# floorctrl_power.net
KiCad netlist of a schematic drawn in Altium Designer
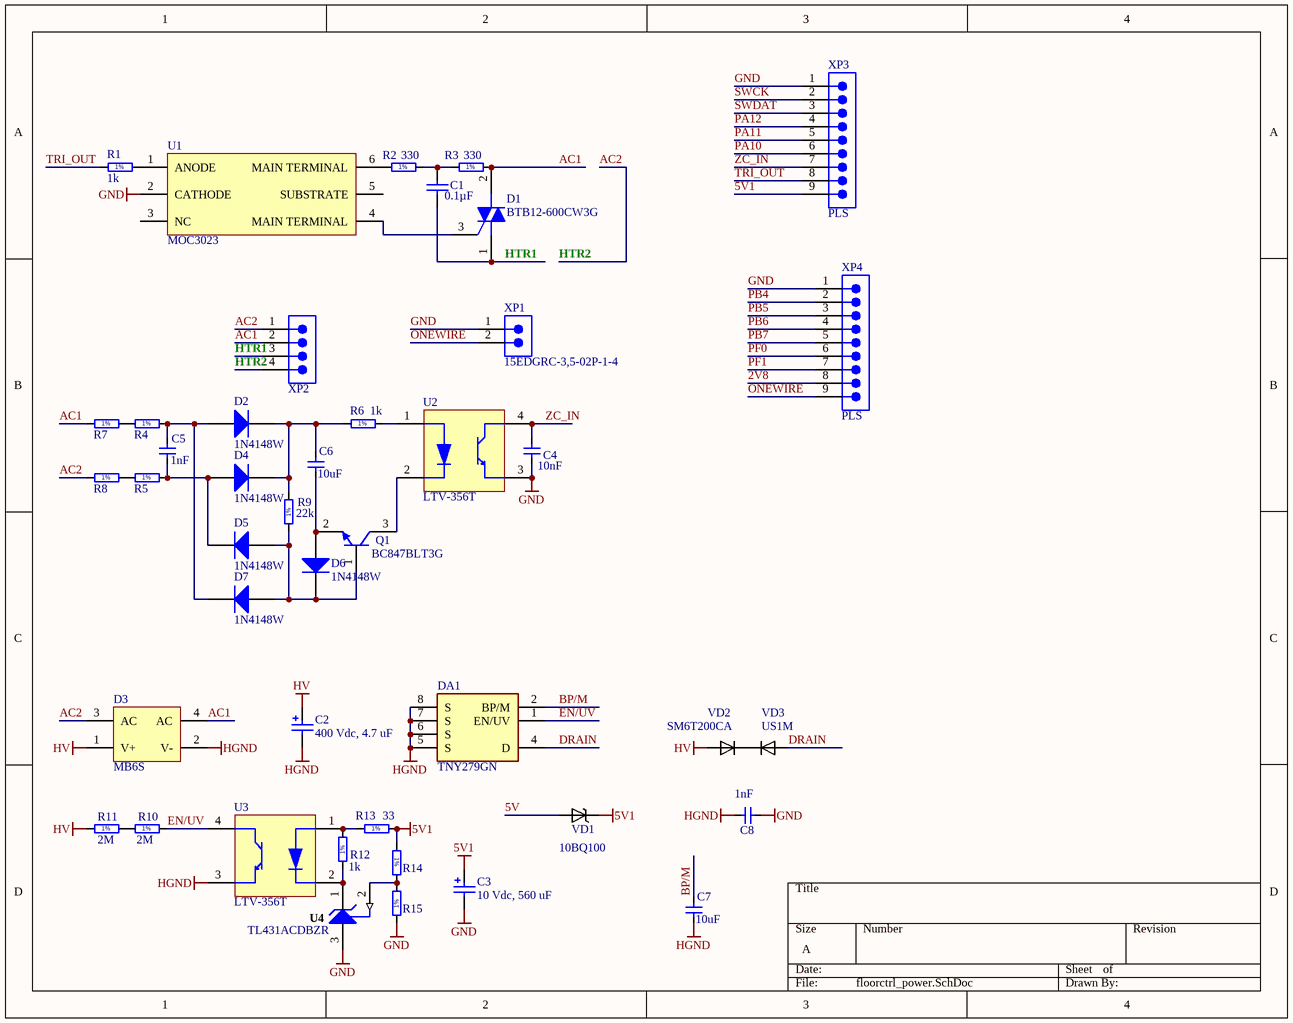
[diagram p0: floorctrl_power.SchDoc]

(export (version "E")
  (design (tool "Eeschema 10.0.6"))
  (components
    (comp (ref "C1")
      (value "A104M15X7RF5TAA")
      (footprint "CAPA55-380X260")
      (fields
        (field (name "MANUFACTURER") "Vishay")
        (field (name "CAPACITANCE") "0.1µF")
        (field (name "TOLERANCE") "±20%")
      )
      (libsource (lib "Altium Content Vault") (part "CAP-NP-2"))
    )
    (comp (ref "C2")
      (value "400 Vdc, 4.7 uF")
      (footprint "WCAP-ATG8_8x11.5x3.5")
      (description "WCAP-ATG8 Aluminum Electrolytic Capacitors, 8x11.5mm, 400 Vdc, 4.7 uF")
      (fields (field (name "PART NUMBER") "860011374005") (field (name "PUBLISHER") "Wurth Elektronik"))
      (libsource (lib "ALTIUM-WCAP-ATG8-rev17a") (part "860011374005"))
    )
    (comp (ref "C3")
      (value "10 Vdc, 560 uF")
      (footprint "WCAP-ATG8_8x11.5x3.5")
      (description "WCAP-ATG8 Aluminum Electrolytic Capacitors, 8x11.5mm, 10 Vdc, 560 uF")
      (fields (field (name "PART NUMBER") "860010274012") (field (name "PUBLISHER") "Wurth Elektronik"))
      (libsource (lib "ALTIUM-WCAP-ATG8-rev17a") (part "860010274012"))
    )
    (comp (ref "C4")
      (value "10nF")
      (footprint "CAP0805R")
      (fields
        (field (name "PART NUMBER") "CC0805_10NF_250V_10%_X7R")
        (field (name "VOLTAGE") "250V")
        (field (name "TOLERANCE") "±10%")
        (field (name "AUTHOR") "I. Kuznetsov")
      )
      (libsource (lib "Capacitor") (part "CAP_NON_POLAR"))
    )
    (comp (ref "C5")
      (value "1nF")
      (footprint "CAP0805R")
      (fields
        (field (name "PART NUMBER") "CC0805_1NF_50V_10%_X7R")
        (field (name "VOLTAGE") "50V")
        (field (name "TOLERANCE") "±10%")
        (field (name "AUTHOR") "I. Kuznetsov")
      )
      (libsource (lib "Capacitor") (part "CAP_NON_POLAR"))
    )
    (comp (ref "C6")
      (value "10uF")
      (footprint "CAP0805R")
      (fields
        (field (name "PART NUMBER") "CC0805_10UF_25V_10%_X5R")
        (field (name "VOLTAGE") "25V")
        (field (name "TOLERANCE") "±10%")
        (field (name "AUTHOR") "I. Kuznetsov")
      )
      (libsource (lib "Capacitor") (part "CAP_NON_POLAR"))
    )
    (comp (ref "C7")
      (value "10uF")
      (footprint "CAP0805R")
      (fields
        (field (name "PART NUMBER") "CC0805_10UF_25V_10%_X5R")
        (field (name "VOLTAGE") "25V")
        (field (name "TOLERANCE") "±10%")
        (field (name "AUTHOR") "I. Kuznetsov")
      )
      (libsource (lib "Capacitor") (part "CAP_NON_POLAR"))
    )
    (comp (ref "C8")
      (value "1nF")
      (footprint "CAP1206R")
      (fields
        (field (name "PART NUMBER") "CC1206_1NF_2KV_10%_X7R")
        (field (name "VOLTAGE") "2kV")
        (field (name "TOLERANCE") "±10%")
        (field (name "AUTHOR") "I. Kuznetsov")
      )
      (libsource (lib "Capacitor") (part "CAP_NON_POLAR"))
    )
    (comp (ref "D1")
      (value "BTB12-600CW3G")
      (footprint "ONSC-TO-220-3-221A-07")
      (description "Triacs, Silicon Bidirectional Thyristor, 3-Pin TO-220, Pb-Free, Tube")
      (fields (field (name "MANUFACTURER") "On Semiconductor"))
      (libsource (lib "Altium Content Vault") (part "ONSC-TRIAC-MT1MT2G-3"))
    )
    (comp (ref "D2")
      (value "1N4148W")
      (footprint "JSCJ-SOD-123-2_V")
      (description "Fast Switching Diode, 75 V, 150 mA, 2-Pin 2.7 x 1.6 x 1.25 mm SMD, Tape and Reel")
      (fields (field (name "MANUFACTURER") "Changjiang Electronics"))
      (libsource (lib "Altium Content Vault") (part "JSCJ-A1K2-2"))
    )
    (comp (ref "D3")
      (value "MB6S")
      (footprint "FAIR-MBXS_V")
      (description "Bridge Rectifier, 0.5 A, -55 to 150 degC, 4-Pin SMD, RoHS, Tape and Reel")
      (fields (field (name "MANUFACTURER") "FairchildSemiconductor"))
      (libsource (lib "Altium Content Vault") (part "FAIR-MBXS-4"))
    )
    (comp (ref "D4")
      (value "1N4148W")
      (footprint "JSCJ-SOD-123-2_V")
      (description "Fast Switching Diode, 75 V, 150 mA, 2-Pin 2.7 x 1.6 x 1.25 mm SMD, Tape and Reel")
      (fields (field (name "MANUFACTURER") "Changjiang Electronics"))
      (libsource (lib "Altium Content Vault") (part "JSCJ-A1K2-2"))
    )
    (comp (ref "D5")
      (value "1N4148W")
      (footprint "JSCJ-SOD-123-2_V")
      (description "Fast Switching Diode, 75 V, 150 mA, 2-Pin 2.7 x 1.6 x 1.25 mm SMD, Tape and Reel")
      (fields (field (name "MANUFACTURER") "Changjiang Electronics"))
      (libsource (lib "Altium Content Vault") (part "JSCJ-A1K2-2"))
    )
    (comp (ref "D6")
      (value "1N4148W")
      (footprint "JSCJ-SOD-123-2_V")
      (description "Fast Switching Diode, 75 V, 150 mA, 2-Pin 2.7 x 1.6 x 1.25 mm SMD, Tape and Reel")
      (fields (field (name "MANUFACTURER") "Changjiang Electronics"))
      (libsource (lib "Altium Content Vault") (part "JSCJ-A1K2-2"))
    )
    (comp (ref "D7")
      (value "1N4148W")
      (footprint "JSCJ-SOD-123-2_V")
      (description "Fast Switching Diode, 75 V, 150 mA, 2-Pin 2.7 x 1.6 x 1.25 mm SMD, Tape and Reel")
      (fields (field (name "MANUFACTURER") "Changjiang Electronics"))
      (libsource (lib "Altium Content Vault") (part "JSCJ-A1K2-2"))
    )
    (comp (ref "DA1")
      (value "TNY279GN")
      (footprint "SMDIP8")
      (libsource (lib "IC And Semiconductor") (part "TNY27x"))
    )
    (comp (ref "Q1")
      (value "BC847BLT3G")
      (footprint "ONSC-SOT-23-3-318-08_V")
      (description "General Purpose Transistor, NPN Silicon, 3-Pin SOT-23, Pb-Free, Tape and Reel")
      (fields (field (name "MANUFACTURER") "On Semiconductor"))
      (libsource (lib "Altium Content Vault") (part "ONSC-NPN-B1E2C3-3"))
    )
    (comp (ref "R1")
      (value "1k")
      (footprint "RES0805R")
      (fields
        (field (name "PART NUMBER") "R0805_1K_1%_0.125W_100PPM")
        (field (name "POWER") "0.125W")
        (field (name "TOLERANCE") "±1%")
        (field (name "AUTHOR") "CERN DEM JLC")
      )
      (libsource (lib "Resistor") (part "Resistor - 1%"))
    )
    (comp (ref "R2")
      (value "330")
      (footprint "RES0805R")
      (fields
        (field (name "PART NUMBER") "R0805_330R_1%_0.125W_100PPM")
        (field (name "POWER") "0.125W")
        (field (name "TOLERANCE") "±1%")
        (field (name "AUTHOR") "CERN DEM JLC")
      )
      (libsource (lib "Resistor") (part "Resistor - 1%"))
    )
    (comp (ref "R3")
      (value "330")
      (footprint "RES0805R")
      (fields
        (field (name "PART NUMBER") "R0805_330R_1%_0.125W_100PPM")
        (field (name "POWER") "0.125W")
        (field (name "TOLERANCE") "±1%")
        (field (name "AUTHOR") "CERN DEM JLC")
      )
      (libsource (lib "Resistor") (part "Resistor - 1%"))
    )
    (comp (ref "R4")
      (value "220k")
      (footprint "RES1206R")
      (fields
        (field (name "PART NUMBER") "R1206_220K_1%_0.25W_100PPM")
        (field (name "POWER") "0.25W")
        (field (name "TOLERANCE") "±1%")
        (field (name "AUTHOR") "CERN DEM JLC")
      )
      (libsource (lib "Resistor") (part "Resistor - 1%"))
    )
    (comp (ref "R5")
      (value "220k")
      (footprint "RES1206R")
      (fields
        (field (name "PART NUMBER") "R1206_220K_1%_0.25W_100PPM")
        (field (name "POWER") "0.25W")
        (field (name "TOLERANCE") "±1%")
        (field (name "AUTHOR") "CERN DEM JLC")
      )
      (libsource (lib "Resistor") (part "Resistor - 1%"))
    )
    (comp (ref "R6")
      (value "1k")
      (footprint "RES0805R")
      (fields
        (field (name "PART NUMBER") "R0805_1K_1%_0.125W_100PPM")
        (field (name "POWER") "0.125W")
        (field (name "TOLERANCE") "±1%")
        (field (name "AUTHOR") "CERN DEM JLC")
      )
      (libsource (lib "Resistor") (part "Resistor - 1%"))
    )
    (comp (ref "R7")
      (value "220k")
      (footprint "RES1206R")
      (fields
        (field (name "PART NUMBER") "R1206_220K_1%_0.25W_100PPM")
        (field (name "POWER") "0.25W")
        (field (name "TOLERANCE") "±1%")
        (field (name "AUTHOR") "CERN DEM JLC")
      )
      (libsource (lib "Resistor") (part "Resistor - 1%"))
    )
    (comp (ref "R8")
      (value "220k")
      (footprint "RES1206R")
      (fields
        (field (name "PART NUMBER") "R1206_220K_1%_0.25W_100PPM")
        (field (name "POWER") "0.25W")
        (field (name "TOLERANCE") "±1%")
        (field (name "AUTHOR") "CERN DEM JLC")
      )
      (libsource (lib "Resistor") (part "Resistor - 1%"))
    )
    (comp (ref "R9")
      (value "22k")
      (footprint "RES0805R")
      (fields
        (field (name "PART NUMBER") "R0805_22K_1%_0.125W_100PPM")
        (field (name "POWER") "0.125W")
        (field (name "TOLERANCE") "±1%")
        (field (name "AUTHOR") "CERN DEM JLC")
      )
      (libsource (lib "Resistor") (part "Resistor - 1%"))
    )
    (comp (ref "R10")
      (value "2M")
      (footprint "RES1206R")
      (fields
        (field (name "PART NUMBER") "R1206_2M_1%_0.25W_100PPM")
        (field (name "POWER") "0.25W")
        (field (name "TOLERANCE") "±1%")
        (field (name "AUTHOR") "CERN DEM JLC")
      )
      (libsource (lib "Resistor") (part "Resistor - 1%"))
    )
    (comp (ref "R11")
      (value "2M")
      (footprint "RES1206R")
      (fields
        (field (name "PART NUMBER") "R1206_2M_1%_0.25W_100PPM")
        (field (name "POWER") "0.25W")
        (field (name "TOLERANCE") "±1%")
        (field (name "AUTHOR") "CERN DEM JLC")
      )
      (libsource (lib "Resistor") (part "Resistor - 1%"))
    )
    (comp (ref "R12")
      (value "1k")
      (footprint "RES0805R")
      (fields
        (field (name "PART NUMBER") "R0805_1K_1%_0.125W_100PPM")
        (field (name "POWER") "0.125W")
        (field (name "TOLERANCE") "±1%")
        (field (name "AUTHOR") "CERN DEM JLC")
      )
      (libsource (lib "Resistor") (part "Resistor - 1%"))
    )
    (comp (ref "R13")
      (value "33")
      (footprint "RES0805R")
      (fields
        (field (name "PART NUMBER") "R0805_33R_1%_0.125W_100PPM")
        (field (name "POWER") "0.125W")
        (field (name "TOLERANCE") "±1%")
        (field (name "AUTHOR") "CERN DEM JLC")
      )
      (libsource (lib "Resistor") (part "Resistor - 1%"))
    )
    (comp (ref "R14")
      (value "10k")
      (footprint "RES0805R")
      (fields
        (field (name "PART NUMBER") "R0805_10K_1%_0.125W_100PPM")
        (field (name "POWER") "0.125W")
        (field (name "TOLERANCE") "±1%")
        (field (name "AUTHOR") "CERN DEM JLC")
      )
      (libsource (lib "Resistor") (part "Resistor - 1%"))
    )
    (comp (ref "R15")
      (value "9k1")
      (footprint "RES0805R")
      (fields
        (field (name "PART NUMBER") "R0805_9K1_1%_0.125W_100PPM")
        (field (name "POWER") "0.125W")
        (field (name "TOLERANCE") "±1%")
        (field (name "AUTHOR") "CERN DEM JLC")
      )
      (libsource (lib "Resistor") (part "Resistor - 1%"))
    )
    (comp (ref "U1")
      (value "MOC3023")
      (footprint "LTST-DIP-6")
      (description "Optocoupler Triac, 50 mA, -40 to 100 degC, 6-Pin DIP, RoHS, Tube")
      (fields (field (name "MANUFACTURER") "Lite-On-Inc."))
      (libsource (lib "Altium Content Vault") (part "LTST-MOC3063-DIP-6"))
    )
    (comp (ref "U2")
      (value "LTV-356T")
      (footprint "LTST-LTV-356T-4_V")
      (description "Optocoupler DC-IN 1-CH Transistor DC-OUT 4-Pin Mini-Flat")
      (fields (field (name "MANUFACTURER") "Lite-On"))
      (libsource (lib "") (part "LTST-LTV-356T-4_1"))
    )
    (comp (ref "U3")
      (value "LTV-356T")
      (footprint "LTST-LTV-356T-4_V")
      (description "Optocoupler DC-IN 1-CH Transistor DC-OUT 4-Pin Mini-Flat")
      (fields (field (name "MANUFACTURER") "Lite-On"))
      (libsource (lib "Altium Content Vault") (part "LTST-LTV-356T-4"))
    )
    (comp (ref "U4")
      (value "TL431ACDBZR")
      (footprint "DBZ0003A_L")
      (fields (field (name "MANUFACTURER") "Texas Instruments"))
      (libsource (lib "Altium Content Vault") (part "TI-TL431ADBZ3"))
    )
    (comp (ref "VD1")
      (value "10BQ100")
      (footprint "DO-214AA")
      (libsource (lib "IC And Semiconductor") (part "Diode - Schottky"))
    )
    (comp (ref "VD2")
      (value "SM6T200CA")
      (footprint "SMB")
      (libsource (lib "IC And Semiconductor") (part "Diode - General"))
    )
    (comp (ref "VD3")
      (value "US1M")
      (footprint "SMA")
      (libsource (lib "IC And Semiconductor") (part "Diode - General"))
    )
    (comp (ref "XP1")
      (value "15EDGRC-3,5-02P-1-4")
      (footprint "15EDGRC-3,5-02P-1-4")
      (libsource (lib "Connector") (part "CN_02P_1W"))
    )
    (comp (ref "XP2")
      (value "15EDGRC-3.5-04P-14")
      (footprint "15EDGRC-3.5-04P")
      (fields (field (name "PART NUMBER") "15EDGRC-3.65-04P-14"))
      (libsource (lib "Connector") (part "CN_04P_1W"))
    )
    (comp (ref "XP3")
      (value "PLS")
      (footprint "PLS-09")
      (fields (field (name "PART NUMBER") "PLS-09") (field (name "MANUFACTURER") "AUK"))
      (libsource (lib "Connector") (part "CN_09P_1W"))
    )
    (comp (ref "XP4")
      (value "PLS")
      (footprint "PLS-09")
      (fields (field (name "PART NUMBER") "PLS-09") (field (name "MANUFACTURER") "AUK"))
      (libsource (lib "Connector") (part "CN_09P_1W"))
    )
  )
  (nets
    (net (code "1") (name "/2V8") (class "Default")
      (node (ref "XP4") (pin "8") (pinfunction "8_8") (pintype "passive"))
    )
    (net (code "2") (name "/5V") (class "Default")
      (node (ref "VD1") (pin "A") (pinfunction "A_A") (pintype "passive"))
    )
    (net (code "3") (name "/AC1") (class "Default")
      (node (ref "D1") (pin "2") (pinfunction "MT2_2") (pintype "passive"))
      (node (ref "D3") (pin "4") (pinfunction "AC_4") (pintype "power_in"))
      (node (ref "R3") (pin "2") (pinfunction "2_2") (pintype "passive"))
      (node (ref "R7") (pin "1") (pinfunction "1_1") (pintype "passive"))
      (node (ref "XP2") (pin "2") (pinfunction "2_2") (pintype "passive"))
    )
    (net (code "4") (name "/AC2") (class "Default")
      (node (ref "D3") (pin "3") (pinfunction "AC_3") (pintype "power_in"))
      (node (ref "R8") (pin "1") (pinfunction "1_1") (pintype "passive"))
      (node (ref "XP2") (pin "1") (pinfunction "1_1") (pintype "passive"))
      (node (ref "XP2") (pin "4") (pinfunction "4_4") (pintype "passive"))
    )
    (net (code "5") (name "/BP{slash}M") (class "Default")
      (node (ref "C7") (pin "2") (pinfunction "2_2") (pintype "passive"))
      (node (ref "DA1") (pin "2") (pinfunction "BP/M_2") (pintype "passive"))
    )
    (net (code "6") (name "/DRAIN") (class "Default")
      (node (ref "DA1") (pin "4") (pinfunction "D_4") (pintype "passive"))
      (node (ref "VD3") (pin "A") (pinfunction "A_A") (pintype "passive"))
    )
    (net (code "7") (name "/EN{slash}UV") (class "Default")
      (node (ref "DA1") (pin "1") (pinfunction "EN/UV_1") (pintype "passive"))
      (node (ref "R10") (pin "2") (pinfunction "2_2") (pintype "passive"))
      (node (ref "U3") (pin "4") (pinfunction "COLLECTOR_4") (pintype "passive"))
    )
    (net (code "8") (name "/HTR1") (class "Default")
      (node (ref "C1") (pin "1") (pinfunction "1_1") (pintype "passive"))
      (node (ref "D1") (pin "1") (pinfunction "MT1_1") (pintype "passive"))
      (node (ref "XP2") (pin "3") (pinfunction "3_3") (pintype "passive"))
    )
    (net (code "9") (name "/ONEWIRE") (class "Default")
      (node (ref "XP1") (pin "2") (pinfunction "2_2") (pintype "passive"))
      (node (ref "XP4") (pin "9") (pinfunction "9_9") (pintype "passive"))
    )
    (net (code "10") (name "/PA10") (class "Default")
      (node (ref "XP3") (pin "6") (pinfunction "6_6") (pintype "passive"))
    )
    (net (code "11") (name "/PA11") (class "Default")
      (node (ref "XP3") (pin "5") (pinfunction "5_5") (pintype "passive"))
    )
    (net (code "12") (name "/PA12") (class "Default")
      (node (ref "XP3") (pin "4") (pinfunction "4_4") (pintype "passive"))
    )
    (net (code "13") (name "/PB4") (class "Default")
      (node (ref "XP4") (pin "2") (pinfunction "2_2") (pintype "passive"))
    )
    (net (code "14") (name "/PB5") (class "Default")
      (node (ref "XP4") (pin "3") (pinfunction "3_3") (pintype "passive"))
    )
    (net (code "15") (name "/PB6") (class "Default")
      (node (ref "XP4") (pin "4") (pinfunction "4_4") (pintype "passive"))
    )
    (net (code "16") (name "/PB7") (class "Default")
      (node (ref "XP4") (pin "5") (pinfunction "5_5") (pintype "passive"))
    )
    (net (code "17") (name "/PF0") (class "Default")
      (node (ref "XP4") (pin "6") (pinfunction "6_6") (pintype "passive"))
    )
    (net (code "18") (name "/PF1") (class "Default")
      (node (ref "XP4") (pin "7") (pinfunction "7_7") (pintype "passive"))
    )
    (net (code "19") (name "/SWCK") (class "Default")
      (node (ref "XP3") (pin "2") (pinfunction "2_2") (pintype "passive"))
    )
    (net (code "20") (name "/SWDAT") (class "Default")
      (node (ref "XP3") (pin "3") (pinfunction "3_3") (pintype "passive"))
    )
    (net (code "21") (name "/TRI_OUT") (class "Default")
      (node (ref "R1") (pin "1") (pinfunction "1_1") (pintype "passive"))
      (node (ref "XP3") (pin "8") (pinfunction "8_8") (pintype "passive"))
    )
    (net (code "22") (name "/ZC_IN") (class "Default")
      (node (ref "C4") (pin "2") (pinfunction "2_2") (pintype "passive"))
      (node (ref "U2") (pin "4") (pinfunction "COLLECTOR_4") (pintype "passive"))
      (node (ref "XP3") (pin "7") (pinfunction "7_7") (pintype "passive"))
    )
    (net (code "23") (name "5V1") (class "Default")
      (node (ref "C3") (pin "1") (pinfunction "P_1") (pintype "passive"))
      (node (ref "R13") (pin "2") (pinfunction "2_2") (pintype "passive"))
      (node (ref "R14") (pin "1") (pinfunction "1_1") (pintype "passive"))
      (node (ref "VD1") (pin "K") (pinfunction "K_K") (pintype "passive"))
      (node (ref "XP3") (pin "9") (pinfunction "9_9") (pintype "passive"))
    )
    (net (code "24") (name "GND") (class "Default")
      (node (ref "C3") (pin "2") (pinfunction "N_2") (pintype "passive"))
      (node (ref "C4") (pin "1") (pinfunction "1_1") (pintype "passive"))
      (node (ref "C8") (pin "2") (pinfunction "2_2") (pintype "passive"))
      (node (ref "R15") (pin "1") (pinfunction "1_1") (pintype "passive"))
      (node (ref "U1") (pin "2") (pinfunction "CATHODE_2") (pintype "passive"))
      (node (ref "U2") (pin "3") (pinfunction "EMITTER_3") (pintype "passive"))
      (node (ref "U4") (pin "3") (pinfunction "ANODE_3") (pintype "passive"))
      (node (ref "XP1") (pin "1") (pinfunction "1_1") (pintype "passive"))
      (node (ref "XP3") (pin "1") (pinfunction "1_1") (pintype "passive"))
      (node (ref "XP4") (pin "1") (pinfunction "1_1") (pintype "passive"))
    )
    (net (code "25") (name "HGND") (class "Default")
      (node (ref "C2") (pin "2") (pinfunction "N_2") (pintype "passive"))
      (node (ref "C7") (pin "1") (pinfunction "1_1") (pintype "passive"))
      (node (ref "C8") (pin "1") (pinfunction "1_1") (pintype "passive"))
      (node (ref "D3") (pin "2") (pinfunction "V-_2") (pintype "power_in"))
      (node (ref "DA1") (pin "5") (pinfunction "S_5") (pintype "passive"))
      (node (ref "DA1") (pin "6") (pinfunction "S_6") (pintype "passive"))
      (node (ref "DA1") (pin "7") (pinfunction "S_7") (pintype "passive"))
      (node (ref "DA1") (pin "8") (pinfunction "S_8") (pintype "passive"))
      (node (ref "U3") (pin "3") (pinfunction "EMITTER_3") (pintype "passive"))
    )
    (net (code "26") (name "HV") (class "Default")
      (node (ref "C2") (pin "1") (pinfunction "P_1") (pintype "passive"))
      (node (ref "D3") (pin "1") (pinfunction "V+_1") (pintype "power_in"))
      (node (ref "R11") (pin "1") (pinfunction "1_1") (pintype "passive"))
      (node (ref "VD2") (pin "A") (pinfunction "A_A") (pintype "passive"))
    )
    (net (code "27") (name "Net-(C1-Pad2)") (class "Default")
      (node (ref "C1") (pin "2") (pinfunction "2_2") (pintype "passive"))
      (node (ref "R2") (pin "2") (pinfunction "2_2") (pintype "passive"))
      (node (ref "R3") (pin "1") (pinfunction "1_1") (pintype "passive"))
    )
    (net (code "28") (name "Net-(D1-G)") (class "Default")
      (node (ref "D1") (pin "3") (pinfunction "G_3") (pintype "passive"))
      (node (ref "U1") (pin "4") (pinfunction "MAIN_TERMINAL_4") (pintype "passive"))
    )
    (net (code "29") (name "Net-(D2-+)") (class "Default")
      (node (ref "C5") (pin "2") (pinfunction "2_2") (pintype "passive"))
      (node (ref "D2") (pin "1") (pinfunction "+_1") (pintype "passive"))
      (node (ref "D7") (pin "2") (pinfunction "-_2") (pintype "passive"))
      (node (ref "R4") (pin "2") (pinfunction "2_2") (pintype "passive"))
    )
    (net (code "30") (name "Net-(D2--)") (class "Default")
      (node (ref "C6") (pin "2") (pinfunction "2_2") (pintype "passive"))
      (node (ref "D2") (pin "2") (pinfunction "-_2") (pintype "passive"))
      (node (ref "D4") (pin "2") (pinfunction "-_2") (pintype "passive"))
      (node (ref "R6") (pin "1") (pinfunction "1_1") (pintype "passive"))
      (node (ref "R9") (pin "2") (pinfunction "2_2") (pintype "passive"))
    )
    (net (code "31") (name "Net-(D4-+)") (class "Default")
      (node (ref "C5") (pin "1") (pinfunction "1_1") (pintype "passive"))
      (node (ref "D4") (pin "1") (pinfunction "+_1") (pintype "passive"))
      (node (ref "D5") (pin "2") (pinfunction "-_2") (pintype "passive"))
      (node (ref "R5") (pin "2") (pinfunction "2_2") (pintype "passive"))
    )
    (net (code "32") (name "Net-(D5-+)") (class "Default")
      (node (ref "D5") (pin "1") (pinfunction "+_1") (pintype "passive"))
      (node (ref "D6") (pin "2") (pinfunction "-_2") (pintype "passive"))
      (node (ref "D7") (pin "1") (pinfunction "+_1") (pintype "passive"))
      (node (ref "Q1") (pin "1") (pinfunction "B_1") (pintype "passive"))
      (node (ref "R9") (pin "1") (pinfunction "1_1") (pintype "passive"))
    )
    (net (code "33") (name "Net-(D6-+)") (class "Default")
      (node (ref "C6") (pin "1") (pinfunction "1_1") (pintype "passive"))
      (node (ref "D6") (pin "1") (pinfunction "+_1") (pintype "passive"))
      (node (ref "Q1") (pin "2") (pinfunction "E_2") (pintype "passive"))
    )
    (net (code "34") (name "Net-(Q1-C)") (class "Default")
      (node (ref "Q1") (pin "3") (pinfunction "C_3") (pintype "passive"))
      (node (ref "U2") (pin "2") (pinfunction "CATHODE_2") (pintype "passive"))
    )
    (net (code "35") (name "Net-(R2-Pad1)") (class "Default")
      (node (ref "R2") (pin "1") (pinfunction "1_1") (pintype "passive"))
      (node (ref "U1") (pin "6") (pinfunction "MAIN_TERMINAL_6") (pintype "passive"))
    )
    (net (code "36") (name "Net-(R4-Pad1)") (class "Default")
      (node (ref "R4") (pin "1") (pinfunction "1_1") (pintype "passive"))
      (node (ref "R7") (pin "2") (pinfunction "2_2") (pintype "passive"))
    )
    (net (code "37") (name "Net-(R5-Pad1)") (class "Default")
      (node (ref "R5") (pin "1") (pinfunction "1_1") (pintype "passive"))
      (node (ref "R8") (pin "2") (pinfunction "2_2") (pintype "passive"))
    )
    (net (code "38") (name "Net-(R10-Pad1)") (class "Default")
      (node (ref "R10") (pin "1") (pinfunction "1_1") (pintype "passive"))
      (node (ref "R11") (pin "2") (pinfunction "2_2") (pintype "passive"))
    )
    (net (code "39") (name "Net-(U1-ANODE)") (class "Default")
      (node (ref "R1") (pin "2") (pinfunction "2_2") (pintype "passive"))
      (node (ref "U1") (pin "1") (pinfunction "ANODE_1") (pintype "passive"))
    )
    (net (code "40") (name "Net-(U2-ANODE)") (class "Default")
      (node (ref "R6") (pin "2") (pinfunction "2_2") (pintype "passive"))
      (node (ref "U2") (pin "1") (pinfunction "ANODE_1") (pintype "passive"))
    )
    (net (code "41") (name "Net-(U3-ANODE)") (class "Default")
      (node (ref "R12") (pin "2") (pinfunction "2_2") (pintype "passive"))
      (node (ref "R13") (pin "1") (pinfunction "1_1") (pintype "passive"))
      (node (ref "U3") (pin "1") (pinfunction "ANODE_1") (pintype "passive"))
    )
    (net (code "42") (name "Net-(U3-CATHODE)") (class "Default")
      (node (ref "R12") (pin "1") (pinfunction "1_1") (pintype "passive"))
      (node (ref "U3") (pin "2") (pinfunction "CATHODE_2") (pintype "passive"))
      (node (ref "U4") (pin "1") (pinfunction "CATHODE_1") (pintype "passive"))
    )
    (net (code "43") (name "Net-(U4-REF)") (class "Default")
      (node (ref "R14") (pin "2") (pinfunction "2_2") (pintype "passive"))
      (node (ref "R15") (pin "2") (pinfunction "2_2") (pintype "passive"))
      (node (ref "U4") (pin "2") (pinfunction "REF_2") (pintype "input"))
    )
    (net (code "44") (name "Net-(VD2-PadK)") (class "Default")
      (node (ref "VD2") (pin "K") (pinfunction "K_K") (pintype "passive"))
      (node (ref "VD3") (pin "K") (pinfunction "K_K") (pintype "passive"))
    )
    (net (code "45") (name "unconnected-(U1-NC-Pad3)") (class "Default")
      (node (ref "U1") (pin "3") (pinfunction "NC_3") (pintype "passive"))
    )
    (net (code "46") (name "unconnected-(U1-SUBSTRATE-Pad5)") (class "Default")
      (node (ref "U1") (pin "5") (pinfunction "SUBSTRATE_5") (pintype "passive"))
    )
  )
)
